# 3w-rgb-led-connector-mk-6_0.net
KiCad netlist of a schematic drawn in EAGLE
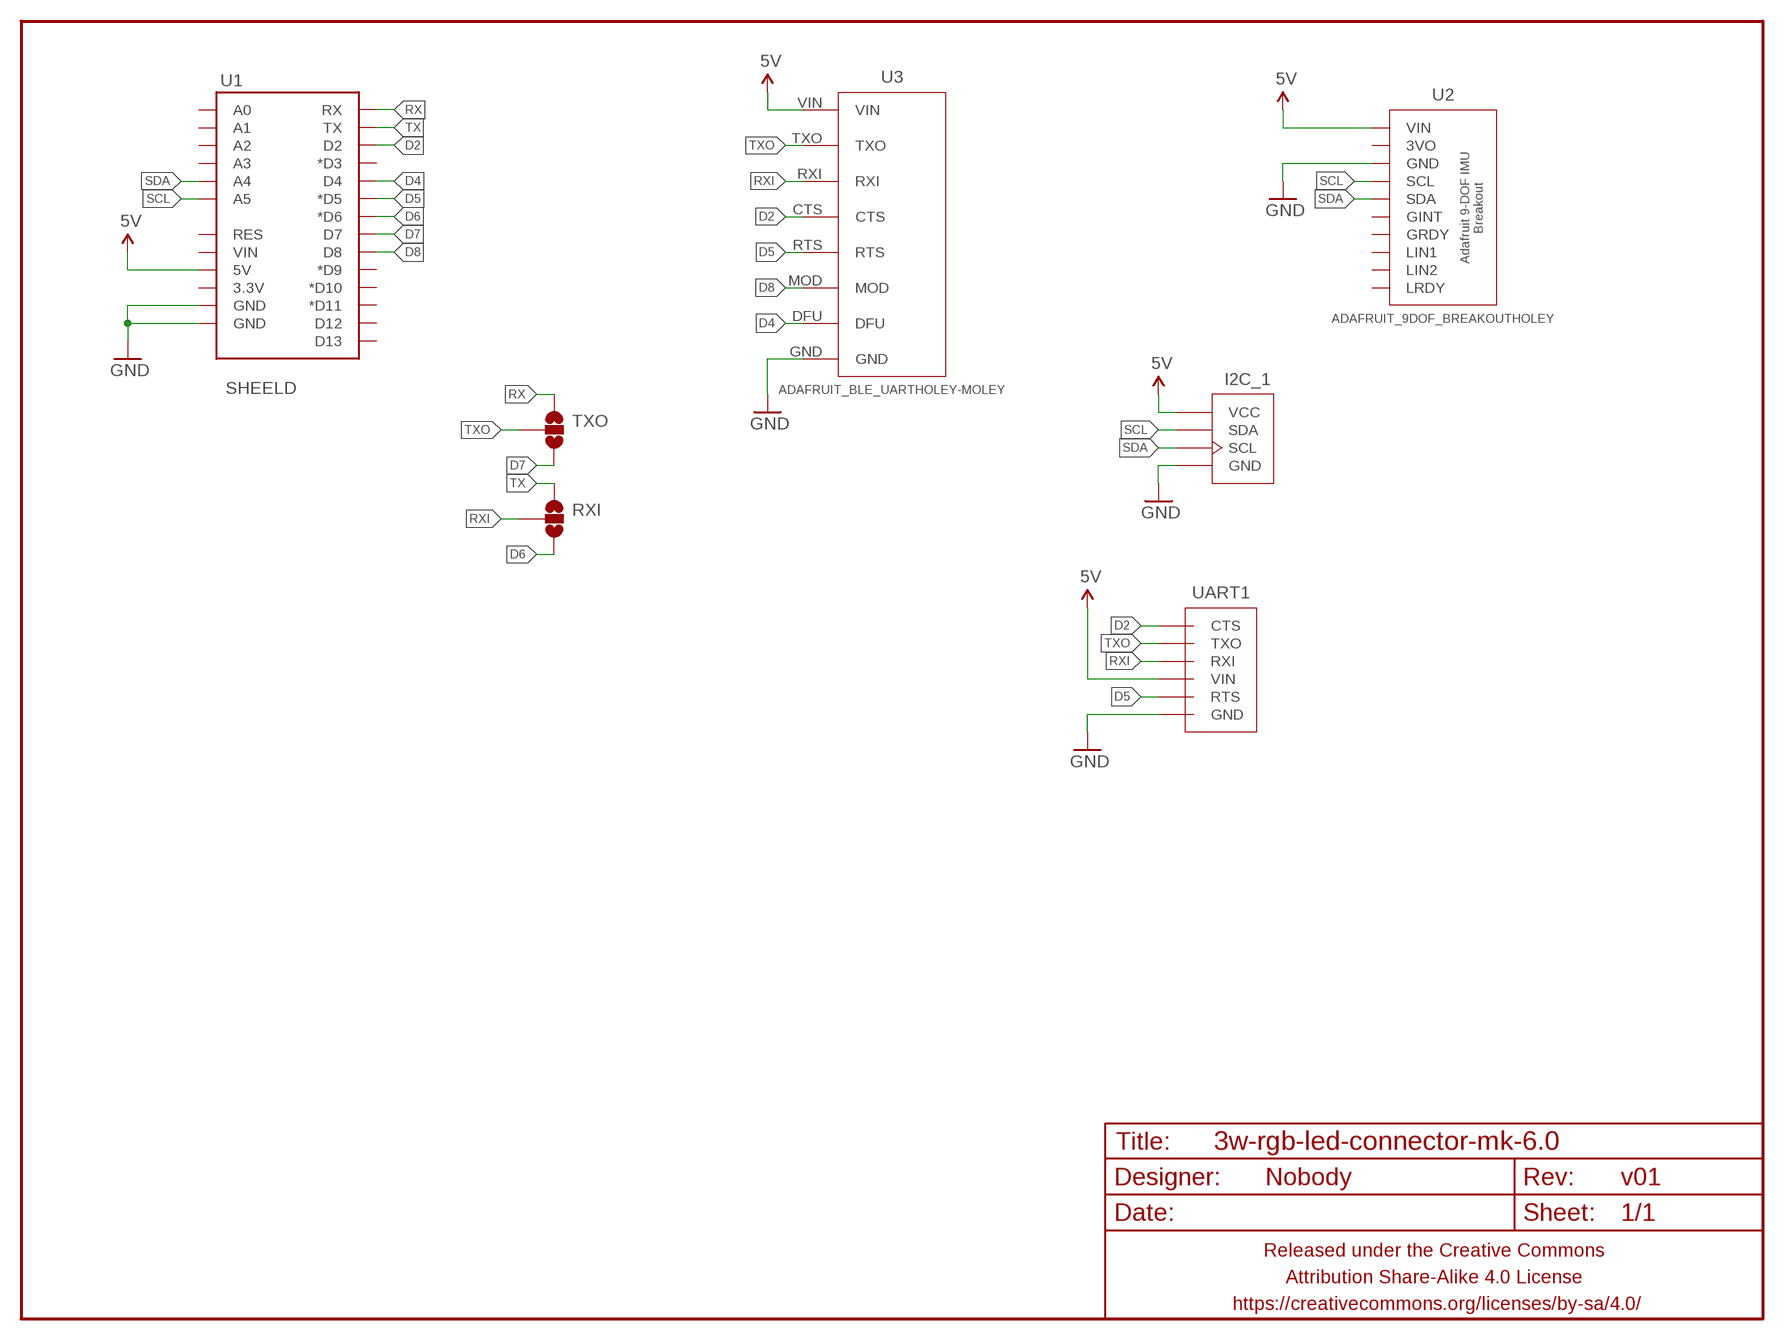
[diagram p0: schematic, sheet 1]

(export (version "E")
  (design (tool "Eeschema 10.0.6"))
  (components
    (comp (ref "FRAME1")
      (value "FRAME-LETTERNO_PACKAGE")
      (footprint "eagle-import:DUMMY")
      (fields (field (name "DESIGNER") "Nobody"))
      (libsource (lib "eagle-import") (part "FRAME-LETTERNO_PACKAGE"))
    )
    (comp (ref "I2C_1")
      (value "M04-I2CPTH-0.1IN")
      (footprint "eagle-import:1X04-PTH-VERT-I2C")
      (libsource (lib "eagle-import") (part "M04-I2CPTH-0.1IN"))
    )
    (comp (ref "RXI")
      (value "JUMPER-PAD-3-NOFULL_BOX_SILK")
      (footprint "eagle-import:PAD-JUMPER-3-NO_YES_SILK_FULL_BOX")
      (libsource (lib "eagle-import") (part "JUMPER-PAD-3-NOFULL_BOX_SILK"))
    )
    (comp (ref "TXO")
      (value "JUMPER-PAD-3-NOFULL_BOX_SILK")
      (footprint "eagle-import:PAD-JUMPER-3-NO_YES_SILK_FULL_BOX")
      (libsource (lib "eagle-import") (part "JUMPER-PAD-3-NOFULL_BOX_SILK"))
    )
    (comp (ref "U1")
      (value "SHEELD")
      (footprint "eagle-import:ARDUINO_SHIELD_NOOUTLINE_INSIDE_SMALLER")
      (libsource (lib "eagle-import") (part "ARDUINO_SHIELD_SMALLER"))
    )
    (comp (ref "U2")
      (value "ADAFRUIT_9DOF_BREAKOUTHOLEY")
      (footprint "eagle-import:ADAFRUIT_9DOF_BREAKOUT_HOLEY")
      (libsource (lib "eagle-import") (part "ADAFRUIT_9DOF_BREAKOUTHOLEY"))
    )
    (comp (ref "U3")
      (value "ADAFRUIT_BLE_UARTHOLEY-MOLEY")
      (footprint "eagle-import:ADAFRUIT_BLE_UART_HOLEY")
      (libsource (lib "eagle-import") (part "ADAFRUIT_BLE_UARTHOLEY-MOLEY"))
    )
    (comp (ref "UART1")
      (value "M06-UARTPTH-0.1IN")
      (footprint "eagle-import:1X06_PTH_UART")
      (libsource (lib "eagle-import") (part "M06-UARTPTH-0.1IN"))
    )
  )
  (nets
    (net (code "1") (name "5V") (class "Default")
      (node (ref "I2C_1") (pin "VCC") (pinfunction "VCC_VCC") (pintype "bidirectional"))
      (node (ref "U1") (pin "5V") (pinfunction "5V_5V") (pintype "bidirectional"))
      (node (ref "U2") (pin "VIN") (pinfunction "VIN_VIN") (pintype "bidirectional"))
      (node (ref "U3") (pin "VIN") (pinfunction "VIN_VIN") (pintype "bidirectional"))
      (node (ref "UART1") (pin "VCC") (pinfunction "VIN_VCC") (pintype "bidirectional"))
    )
    (net (code "2") (name "D2") (class "Default")
      (node (ref "U1") (pin "D2") (pinfunction "D2_D2") (pintype "bidirectional"))
      (node (ref "U3") (pin "CTS") (pinfunction "CTS_CTS") (pintype "bidirectional"))
      (node (ref "UART1") (pin "CTS") (pinfunction "CTS_CTS") (pintype "bidirectional"))
    )
    (net (code "3") (name "D4") (class "Default")
      (node (ref "U1") (pin "D4") (pinfunction "D4_D4") (pintype "bidirectional"))
      (node (ref "U3") (pin "DFU") (pinfunction "DFU_DFU") (pintype "bidirectional"))
    )
    (net (code "4") (name "D5") (class "Default")
      (node (ref "U1") (pin "D5") (pinfunction "*D5_D5") (pintype "bidirectional"))
      (node (ref "U3") (pin "RTS") (pinfunction "RTS_RTS") (pintype "bidirectional"))
      (node (ref "UART1") (pin "RTS") (pinfunction "RTS_RTS") (pintype "bidirectional"))
    )
    (net (code "5") (name "D6") (class "Default")
      (node (ref "RXI") (pin "3") (pinfunction "3_3") (pintype "passive"))
      (node (ref "U1") (pin "D6") (pinfunction "*D6_D6") (pintype "bidirectional"))
    )
    (net (code "6") (name "D7") (class "Default")
      (node (ref "TXO") (pin "3") (pinfunction "3_3") (pintype "passive"))
      (node (ref "U1") (pin "D7") (pinfunction "D7_D7") (pintype "bidirectional"))
    )
    (net (code "7") (name "D8") (class "Default")
      (node (ref "U1") (pin "D8") (pinfunction "D8_D8") (pintype "bidirectional"))
      (node (ref "U3") (pin "MOD") (pinfunction "MOD_MOD") (pintype "bidirectional"))
    )
    (net (code "8") (name "GND") (class "Default")
      (node (ref "I2C_1") (pin "GND") (pinfunction "GND_GND") (pintype "bidirectional"))
      (node (ref "U1") (pin "GND@0") (pinfunction "GND_GND@0") (pintype "bidirectional"))
      (node (ref "U1") (pin "GND@1") (pinfunction "GND_GND@1") (pintype "bidirectional"))
      (node (ref "U2") (pin "GND") (pinfunction "GND_GND") (pintype "bidirectional"))
      (node (ref "U3") (pin "GND") (pinfunction "GND_GND") (pintype "bidirectional"))
      (node (ref "UART1") (pin "GND") (pinfunction "GND_GND") (pintype "bidirectional"))
    )
    (net (code "9") (name "RX") (class "Default")
      (node (ref "TXO") (pin "1") (pinfunction "1_1") (pintype "passive"))
      (node (ref "U1") (pin "RX") (pinfunction "RX_RX") (pintype "bidirectional"))
    )
    (net (code "10") (name "RXI") (class "Default")
      (node (ref "RXI") (pin "2") (pinfunction "2_2") (pintype "passive"))
      (node (ref "U3") (pin "RXI") (pinfunction "RXI_RXI") (pintype "bidirectional"))
      (node (ref "UART1") (pin "RXI") (pinfunction "RXI_RXI") (pintype "bidirectional"))
    )
    (net (code "11") (name "SCL") (class "Default")
      (node (ref "I2C_1") (pin "SDA") (pinfunction "SDA_SDA") (pintype "bidirectional"))
      (node (ref "U1") (pin "A5") (pinfunction "A5_A5") (pintype "bidirectional"))
      (node (ref "U2") (pin "SCL") (pinfunction "SCL_SCL") (pintype "bidirectional"))
    )
    (net (code "12") (name "SDA") (class "Default")
      (node (ref "I2C_1") (pin "SCL") (pinfunction "SCL_SCL") (pintype "bidirectional"))
      (node (ref "U1") (pin "A4") (pinfunction "A4_A4") (pintype "bidirectional"))
      (node (ref "U2") (pin "SDA") (pinfunction "SDA_SDA") (pintype "bidirectional"))
    )
    (net (code "13") (name "TX") (class "Default")
      (node (ref "RXI") (pin "1") (pinfunction "1_1") (pintype "passive"))
      (node (ref "U1") (pin "TX") (pinfunction "TX_TX") (pintype "bidirectional"))
    )
    (net (code "14") (name "TXO") (class "Default")
      (node (ref "TXO") (pin "2") (pinfunction "2_2") (pintype "passive"))
      (node (ref "U3") (pin "TXO") (pinfunction "TXO_TXO") (pintype "bidirectional"))
      (node (ref "UART1") (pin "TXO") (pinfunction "TXO_TXO") (pintype "bidirectional"))
    )
    (net (code "15") (name "unconnected-(U1-*D3-PadD3)") (class "Default")
      (node (ref "U1") (pin "D3") (pinfunction "*D3_D3") (pintype "bidirectional"))
    )
    (net (code "16") (name "unconnected-(U1-*D9-PadD9)") (class "Default")
      (node (ref "U1") (pin "D9") (pinfunction "*D9_D9") (pintype "bidirectional"))
    )
    (net (code "17") (name "unconnected-(U1-*D10-PadD10)") (class "Default")
      (node (ref "U1") (pin "D10") (pinfunction "*D10_D10") (pintype "bidirectional"))
    )
    (net (code "18") (name "unconnected-(U1-*D11-PadD11)") (class "Default")
      (node (ref "U1") (pin "D11") (pinfunction "*D11_D11") (pintype "bidirectional"))
    )
    (net (code "19") (name "unconnected-(U1-Pad3.3V)") (class "Default")
      (node (ref "U1") (pin "3.3V") (pinfunction "3.3V_3.3V") (pintype "bidirectional"))
    )
    (net (code "20") (name "unconnected-(U1-PadA0)") (class "Default")
      (node (ref "U1") (pin "A0") (pinfunction "A0_A0") (pintype "bidirectional"))
    )
    (net (code "21") (name "unconnected-(U1-PadA1)") (class "Default")
      (node (ref "U1") (pin "A1") (pinfunction "A1_A1") (pintype "bidirectional"))
    )
    (net (code "22") (name "unconnected-(U1-PadA2)") (class "Default")
      (node (ref "U1") (pin "A2") (pinfunction "A2_A2") (pintype "bidirectional"))
    )
    (net (code "23") (name "unconnected-(U1-PadA3)") (class "Default")
      (node (ref "U1") (pin "A3") (pinfunction "A3_A3") (pintype "bidirectional"))
    )
    (net (code "24") (name "unconnected-(U1-PadD12)") (class "Default")
      (node (ref "U1") (pin "D12") (pinfunction "D12_D12") (pintype "bidirectional"))
    )
    (net (code "25") (name "unconnected-(U1-PadD13)") (class "Default")
      (node (ref "U1") (pin "D13") (pinfunction "D13_D13") (pintype "bidirectional"))
    )
    (net (code "26") (name "unconnected-(U1-PadRES)") (class "Default")
      (node (ref "U1") (pin "RES") (pinfunction "RES_RES") (pintype "bidirectional"))
    )
    (net (code "27") (name "unconnected-(U1-PadVIN)") (class "Default")
      (node (ref "U1") (pin "VIN") (pinfunction "VIN_VIN") (pintype "bidirectional"))
    )
    (net (code "28") (name "unconnected-(U2-Pad3VO)") (class "Default")
      (node (ref "U2") (pin "3VO") (pinfunction "3VO_3VO") (pintype "bidirectional"))
    )
    (net (code "29") (name "unconnected-(U2-PadGINT)") (class "Default")
      (node (ref "U2") (pin "GINT") (pinfunction "GINT_GINT") (pintype "bidirectional"))
    )
    (net (code "30") (name "unconnected-(U2-PadGRDY)") (class "Default")
      (node (ref "U2") (pin "GRDY") (pinfunction "GRDY_GRDY") (pintype "bidirectional"))
    )
    (net (code "31") (name "unconnected-(U2-PadLIN1)") (class "Default")
      (node (ref "U2") (pin "LIN1") (pinfunction "LIN1_LIN1") (pintype "bidirectional"))
    )
    (net (code "32") (name "unconnected-(U2-PadLIN2)") (class "Default")
      (node (ref "U2") (pin "LIN2") (pinfunction "LIN2_LIN2") (pintype "bidirectional"))
    )
    (net (code "33") (name "unconnected-(U2-PadLRDY)") (class "Default")
      (node (ref "U2") (pin "LRDY") (pinfunction "LRDY_LRDY") (pintype "bidirectional"))
    )
  )
)
